# CHIP_Shield.net
KiCad netlist of a schematic drawn in EAGLE
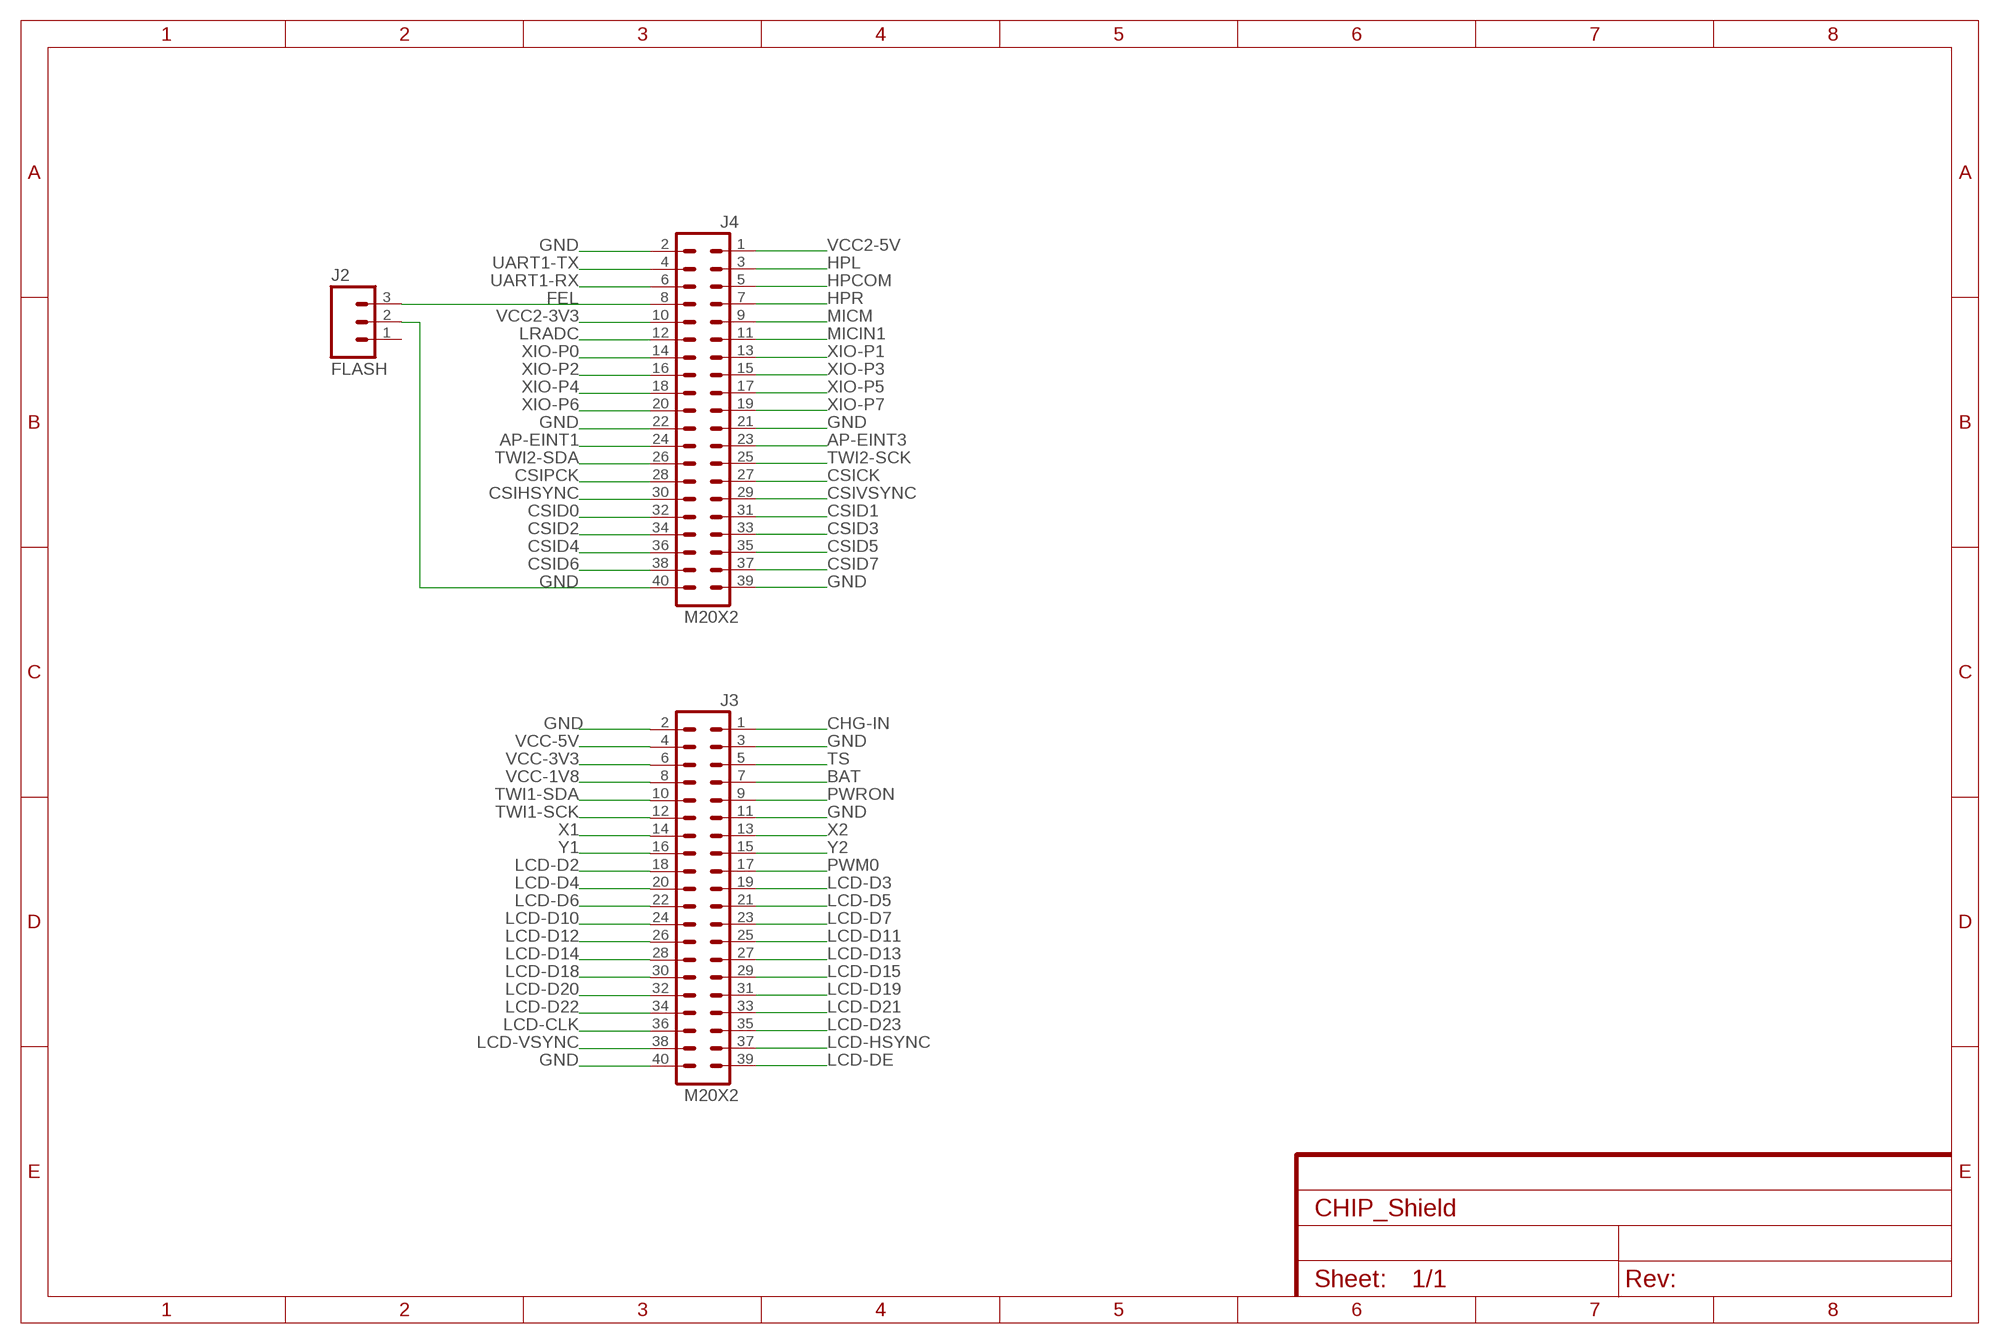
[diagram p0: schematic, sheet 1]

(export (version "E")
  (design (tool "Eeschema 10.0.6"))
  (components
    (comp (ref "J2")
      (value "FLASH")
      (footprint "eagle-import:1X03")
      (libsource (lib "eagle-import") (part "M03PTH"))
    )
    (comp (ref "J3")
      (value "M20X2")
      (footprint "eagle-import:2X20")
      (libsource (lib "eagle-import") (part "M20X2"))
    )
    (comp (ref "J4")
      (value "M20X2")
      (footprint "eagle-import:2X20")
      (libsource (lib "eagle-import") (part "M20X2"))
    )
  )
  (nets
    (net (code "1") (name "/AP-EINT1") (class "Default")
      (node (ref "J4") (pin "24") (pinfunction "24_24") (pintype "passive"))
    )
    (net (code "2") (name "/AP-EINT3") (class "Default")
      (node (ref "J4") (pin "23") (pinfunction "23_23") (pintype "passive"))
    )
    (net (code "3") (name "/BAT") (class "Default")
      (node (ref "J3") (pin "7") (pinfunction "7_7") (pintype "passive"))
    )
    (net (code "4") (name "/CHG-IN") (class "Default")
      (node (ref "J3") (pin "1") (pinfunction "1_1") (pintype "passive"))
    )
    (net (code "5") (name "/CSICK") (class "Default")
      (node (ref "J4") (pin "27") (pinfunction "27_27") (pintype "passive"))
    )
    (net (code "6") (name "/CSID0") (class "Default")
      (node (ref "J4") (pin "32") (pinfunction "32_32") (pintype "passive"))
    )
    (net (code "7") (name "/CSID1") (class "Default")
      (node (ref "J4") (pin "31") (pinfunction "31_31") (pintype "passive"))
    )
    (net (code "8") (name "/CSID2") (class "Default")
      (node (ref "J4") (pin "34") (pinfunction "34_34") (pintype "passive"))
    )
    (net (code "9") (name "/CSID3") (class "Default")
      (node (ref "J4") (pin "33") (pinfunction "33_33") (pintype "passive"))
    )
    (net (code "10") (name "/CSID4") (class "Default")
      (node (ref "J4") (pin "36") (pinfunction "36_36") (pintype "passive"))
    )
    (net (code "11") (name "/CSID5") (class "Default")
      (node (ref "J4") (pin "35") (pinfunction "35_35") (pintype "passive"))
    )
    (net (code "12") (name "/CSID6") (class "Default")
      (node (ref "J4") (pin "38") (pinfunction "38_38") (pintype "passive"))
    )
    (net (code "13") (name "/CSID7") (class "Default")
      (node (ref "J4") (pin "37") (pinfunction "37_37") (pintype "passive"))
    )
    (net (code "14") (name "/CSIHSYNC") (class "Default")
      (node (ref "J4") (pin "30") (pinfunction "30_30") (pintype "passive"))
    )
    (net (code "15") (name "/CSIPCK") (class "Default")
      (node (ref "J4") (pin "28") (pinfunction "28_28") (pintype "passive"))
    )
    (net (code "16") (name "/CSIVSYNC") (class "Default")
      (node (ref "J4") (pin "29") (pinfunction "29_29") (pintype "passive"))
    )
    (net (code "17") (name "/FEL") (class "Default")
      (node (ref "J2") (pin "3") (pinfunction "3_3") (pintype "passive"))
      (node (ref "J4") (pin "8") (pinfunction "8_8") (pintype "passive"))
    )
    (net (code "18") (name "/GND") (class "Default")
      (node (ref "J2") (pin "2") (pinfunction "2_2") (pintype "passive"))
      (node (ref "J3") (pin "11") (pinfunction "11_11") (pintype "passive"))
      (node (ref "J3") (pin "2") (pinfunction "2_2") (pintype "passive"))
      (node (ref "J3") (pin "3") (pinfunction "3_3") (pintype "passive"))
      (node (ref "J3") (pin "40") (pinfunction "40_40") (pintype "passive"))
      (node (ref "J4") (pin "2") (pinfunction "2_2") (pintype "passive"))
      (node (ref "J4") (pin "21") (pinfunction "21_21") (pintype "passive"))
      (node (ref "J4") (pin "22") (pinfunction "22_22") (pintype "passive"))
      (node (ref "J4") (pin "39") (pinfunction "39_39") (pintype "passive"))
      (node (ref "J4") (pin "40") (pinfunction "40_40") (pintype "passive"))
    )
    (net (code "19") (name "/HPCOM") (class "Default")
      (node (ref "J4") (pin "5") (pinfunction "5_5") (pintype "passive"))
    )
    (net (code "20") (name "/HPL") (class "Default")
      (node (ref "J4") (pin "3") (pinfunction "3_3") (pintype "passive"))
    )
    (net (code "21") (name "/HPR") (class "Default")
      (node (ref "J4") (pin "7") (pinfunction "7_7") (pintype "passive"))
    )
    (net (code "22") (name "/LCD-CLK") (class "Default")
      (node (ref "J3") (pin "36") (pinfunction "36_36") (pintype "passive"))
    )
    (net (code "23") (name "/LCD-D2") (class "Default")
      (node (ref "J3") (pin "18") (pinfunction "18_18") (pintype "passive"))
    )
    (net (code "24") (name "/LCD-D3") (class "Default")
      (node (ref "J3") (pin "19") (pinfunction "19_19") (pintype "passive"))
    )
    (net (code "25") (name "/LCD-D4") (class "Default")
      (node (ref "J3") (pin "20") (pinfunction "20_20") (pintype "passive"))
    )
    (net (code "26") (name "/LCD-D5") (class "Default")
      (node (ref "J3") (pin "21") (pinfunction "21_21") (pintype "passive"))
    )
    (net (code "27") (name "/LCD-D6") (class "Default")
      (node (ref "J3") (pin "22") (pinfunction "22_22") (pintype "passive"))
    )
    (net (code "28") (name "/LCD-D7") (class "Default")
      (node (ref "J3") (pin "23") (pinfunction "23_23") (pintype "passive"))
    )
    (net (code "29") (name "/LCD-D10") (class "Default")
      (node (ref "J3") (pin "24") (pinfunction "24_24") (pintype "passive"))
    )
    (net (code "30") (name "/LCD-D11") (class "Default")
      (node (ref "J3") (pin "25") (pinfunction "25_25") (pintype "passive"))
    )
    (net (code "31") (name "/LCD-D12") (class "Default")
      (node (ref "J3") (pin "26") (pinfunction "26_26") (pintype "passive"))
    )
    (net (code "32") (name "/LCD-D13") (class "Default")
      (node (ref "J3") (pin "27") (pinfunction "27_27") (pintype "passive"))
    )
    (net (code "33") (name "/LCD-D14") (class "Default")
      (node (ref "J3") (pin "28") (pinfunction "28_28") (pintype "passive"))
    )
    (net (code "34") (name "/LCD-D15") (class "Default")
      (node (ref "J3") (pin "29") (pinfunction "29_29") (pintype "passive"))
    )
    (net (code "35") (name "/LCD-D18") (class "Default")
      (node (ref "J3") (pin "30") (pinfunction "30_30") (pintype "passive"))
    )
    (net (code "36") (name "/LCD-D19") (class "Default")
      (node (ref "J3") (pin "31") (pinfunction "31_31") (pintype "passive"))
    )
    (net (code "37") (name "/LCD-D20") (class "Default")
      (node (ref "J3") (pin "32") (pinfunction "32_32") (pintype "passive"))
    )
    (net (code "38") (name "/LCD-D21") (class "Default")
      (node (ref "J3") (pin "33") (pinfunction "33_33") (pintype "passive"))
    )
    (net (code "39") (name "/LCD-D22") (class "Default")
      (node (ref "J3") (pin "34") (pinfunction "34_34") (pintype "passive"))
    )
    (net (code "40") (name "/LCD-D23") (class "Default")
      (node (ref "J3") (pin "35") (pinfunction "35_35") (pintype "passive"))
    )
    (net (code "41") (name "/LCD-DE") (class "Default")
      (node (ref "J3") (pin "39") (pinfunction "39_39") (pintype "passive"))
    )
    (net (code "42") (name "/LCD-HSYNC") (class "Default")
      (node (ref "J3") (pin "37") (pinfunction "37_37") (pintype "passive"))
    )
    (net (code "43") (name "/LCD-VSYNC") (class "Default")
      (node (ref "J3") (pin "38") (pinfunction "38_38") (pintype "passive"))
    )
    (net (code "44") (name "/LRADC") (class "Default")
      (node (ref "J4") (pin "12") (pinfunction "12_12") (pintype "passive"))
    )
    (net (code "45") (name "/MICIN1") (class "Default")
      (node (ref "J4") (pin "11") (pinfunction "11_11") (pintype "passive"))
    )
    (net (code "46") (name "/MICM") (class "Default")
      (node (ref "J4") (pin "9") (pinfunction "9_9") (pintype "passive"))
    )
    (net (code "47") (name "/PWM0") (class "Default")
      (node (ref "J3") (pin "17") (pinfunction "17_17") (pintype "passive"))
    )
    (net (code "48") (name "/PWRON") (class "Default")
      (node (ref "J3") (pin "9") (pinfunction "9_9") (pintype "passive"))
    )
    (net (code "49") (name "/TS") (class "Default")
      (node (ref "J3") (pin "5") (pinfunction "5_5") (pintype "passive"))
    )
    (net (code "50") (name "/TWI1-SCK") (class "Default")
      (node (ref "J3") (pin "12") (pinfunction "12_12") (pintype "passive"))
    )
    (net (code "51") (name "/TWI1-SDA") (class "Default")
      (node (ref "J3") (pin "10") (pinfunction "10_10") (pintype "passive"))
    )
    (net (code "52") (name "/TWI2-SCK") (class "Default")
      (node (ref "J4") (pin "25") (pinfunction "25_25") (pintype "passive"))
    )
    (net (code "53") (name "/TWI2-SDA") (class "Default")
      (node (ref "J4") (pin "26") (pinfunction "26_26") (pintype "passive"))
    )
    (net (code "54") (name "/UART1-RX") (class "Default")
      (node (ref "J4") (pin "6") (pinfunction "6_6") (pintype "passive"))
    )
    (net (code "55") (name "/UART1-TX") (class "Default")
      (node (ref "J4") (pin "4") (pinfunction "4_4") (pintype "passive"))
    )
    (net (code "56") (name "/VCC-1V8") (class "Default")
      (node (ref "J3") (pin "8") (pinfunction "8_8") (pintype "passive"))
    )
    (net (code "57") (name "/VCC-3V3") (class "Default")
      (node (ref "J3") (pin "6") (pinfunction "6_6") (pintype "passive"))
    )
    (net (code "58") (name "/VCC-5V") (class "Default")
      (node (ref "J3") (pin "4") (pinfunction "4_4") (pintype "passive"))
    )
    (net (code "59") (name "/VCC2-3V3") (class "Default")
      (node (ref "J4") (pin "10") (pinfunction "10_10") (pintype "passive"))
    )
    (net (code "60") (name "/VCC2-5V") (class "Default")
      (node (ref "J4") (pin "1") (pinfunction "1_1") (pintype "passive"))
    )
    (net (code "61") (name "/X1") (class "Default")
      (node (ref "J3") (pin "14") (pinfunction "14_14") (pintype "passive"))
    )
    (net (code "62") (name "/X2") (class "Default")
      (node (ref "J3") (pin "13") (pinfunction "13_13") (pintype "passive"))
    )
    (net (code "63") (name "/XIO-P0") (class "Default")
      (node (ref "J4") (pin "14") (pinfunction "14_14") (pintype "passive"))
    )
    (net (code "64") (name "/XIO-P1") (class "Default")
      (node (ref "J4") (pin "13") (pinfunction "13_13") (pintype "passive"))
    )
    (net (code "65") (name "/XIO-P2") (class "Default")
      (node (ref "J4") (pin "16") (pinfunction "16_16") (pintype "passive"))
    )
    (net (code "66") (name "/XIO-P3") (class "Default")
      (node (ref "J4") (pin "15") (pinfunction "15_15") (pintype "passive"))
    )
    (net (code "67") (name "/XIO-P4") (class "Default")
      (node (ref "J4") (pin "18") (pinfunction "18_18") (pintype "passive"))
    )
    (net (code "68") (name "/XIO-P5") (class "Default")
      (node (ref "J4") (pin "17") (pinfunction "17_17") (pintype "passive"))
    )
    (net (code "69") (name "/XIO-P6") (class "Default")
      (node (ref "J4") (pin "20") (pinfunction "20_20") (pintype "passive"))
    )
    (net (code "70") (name "/XIO-P7") (class "Default")
      (node (ref "J4") (pin "19") (pinfunction "19_19") (pintype "passive"))
    )
    (net (code "71") (name "/Y1") (class "Default")
      (node (ref "J3") (pin "16") (pinfunction "16_16") (pintype "passive"))
    )
    (net (code "72") (name "/Y2") (class "Default")
      (node (ref "J3") (pin "15") (pinfunction "15_15") (pintype "passive"))
    )
    (net (code "73") (name "unconnected-(J2-Pad1)") (class "Default")
      (node (ref "J2") (pin "1") (pinfunction "1_1") (pintype "passive"))
    )
  )
)
